# IRBeaconBlasterSchematic.net
KiCad netlist of a schematic drawn in Altium Designer
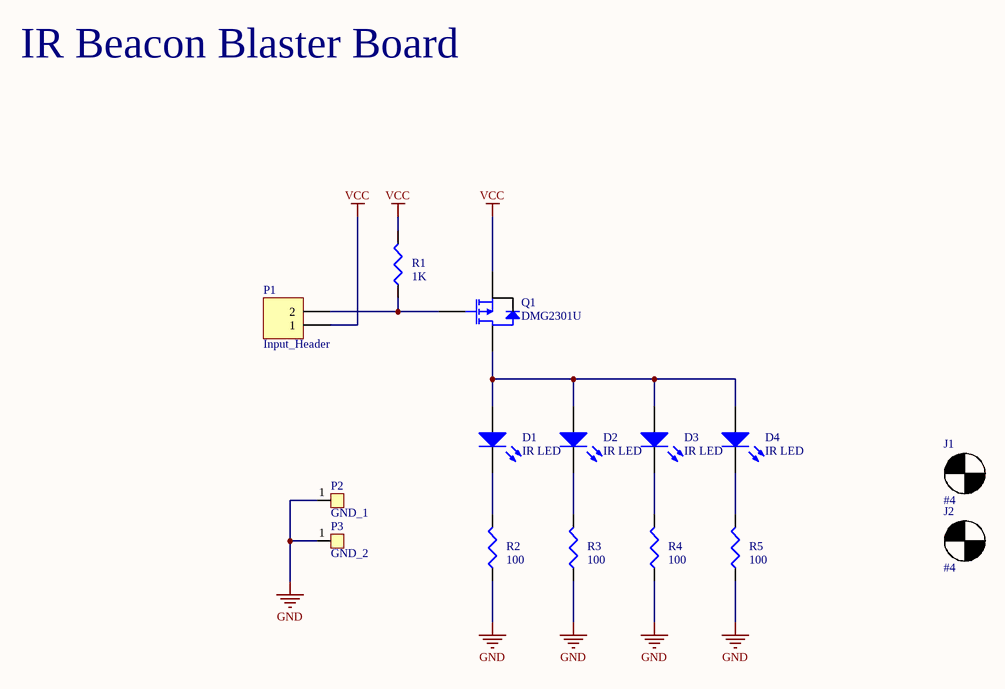
[diagram p0: IRBeaconBlasterSchematic.SchDoc]

(export (version "E")
  (design (tool "Eeschema 10.0.6"))
  (components
    (comp (ref "D1") (value "IR LED") (footprint "LED_PTH_3mm") (libsource (lib "mrone") (part "LED")))
    (comp (ref "D2") (value "IR LED") (footprint "LED_PTH_3mm") (libsource (lib "mrone") (part "LED")))
    (comp (ref "D3") (value "IR LED") (footprint "LED_PTH_3mm") (libsource (lib "mrone") (part "LED")))
    (comp (ref "D4") (value "IR LED") (footprint "LED_PTH_3mm") (libsource (lib "mrone") (part "LED")))
    (comp (ref "J1")
      (value "#4")
      (footprint "#4_Screw_Hole")
      (description "A mechanical hole for mounting the board")
      (libsource (lib "mrone") (part "Mechanical_Hole"))
    )
    (comp (ref "J2")
      (value "#4")
      (footprint "#4_Screw_Hole")
      (description "A mechanical hole for mounting the board")
      (libsource (lib "mrone") (part "Mechanical_Hole"))
    )
    (comp (ref "P1")
      (value "Input_Header")
      (footprint "HDR1X2")
      (description "Header, 2-Pin")
      (fields (field (name "PUBLISHER") "Altium Limited"))
      (libsource (lib "mrone") (part "Header 2"))
    )
    (comp (ref "P2") (value "GND_1") (footprint "HDR1X1") (libsource (lib "mrone") (part "Header 1x1")))
    (comp (ref "P3") (value "GND_2") (footprint "HDR1X1") (libsource (lib "mrone") (part "Header 1x1")))
    (comp (ref "Q1") (value "DMG2301U") (footprint "SOT-23") (libsource (lib "mrone") (part "P-Mosfet")))
    (comp (ref "R1")
      (value "1K")
      (footprint "J1-0603")
      (description "Resistor")
      (fields (field (name "PUBLISHER") "Altium Limited"))
      (libsource (lib "Miscellaneous Devices") (part "Res3"))
    )
    (comp (ref "R2")
      (value "100")
      (footprint "J1-0603")
      (description "Resistor")
      (fields (field (name "Comment") "Res3") (field (name "PUBLISHER") "Altium Limited"))
      (libsource (lib "Miscellaneous Devices") (part "Res3"))
    )
    (comp (ref "R3")
      (value "100")
      (footprint "J1-0603")
      (description "Resistor")
      (fields (field (name "Comment") "Res3") (field (name "PUBLISHER") "Altium Limited"))
      (libsource (lib "Miscellaneous Devices") (part "Res3"))
    )
    (comp (ref "R4")
      (value "100")
      (footprint "J1-0603")
      (description "Resistor")
      (fields (field (name "Comment") "Res3") (field (name "PUBLISHER") "Altium Limited"))
      (libsource (lib "Miscellaneous Devices") (part "Res3"))
    )
    (comp (ref "R5")
      (value "100")
      (footprint "J1-0603")
      (description "Resistor")
      (fields (field (name "Comment") "Res3") (field (name "PUBLISHER") "Altium Limited"))
      (libsource (lib "Miscellaneous Devices") (part "Res3"))
    )
  )
  (nets
    (net (code "1") (name "GND") (class "Default")
      (node (ref "P2") (pin "1") (pintype "passive"))
      (node (ref "P3") (pin "1") (pintype "passive"))
      (node (ref "R2") (pin "1") (pinfunction "1_1") (pintype "passive"))
      (node (ref "R3") (pin "1") (pinfunction "1_1") (pintype "passive"))
      (node (ref "R4") (pin "1") (pinfunction "1_1") (pintype "passive"))
      (node (ref "R5") (pin "1") (pinfunction "1_1") (pintype "passive"))
    )
    (net (code "2") (name "Net-(D1-A)") (class "Default")
      (node (ref "D1") (pin "1") (pinfunction "A_1") (pintype "passive"))
      (node (ref "D2") (pin "1") (pinfunction "A_1") (pintype "passive"))
      (node (ref "D3") (pin "1") (pinfunction "A_1") (pintype "passive"))
      (node (ref "D4") (pin "1") (pinfunction "A_1") (pintype "passive"))
      (node (ref "Q1") (pin "3") (pinfunction "D_3") (pintype "passive"))
    )
    (net (code "3") (name "Net-(D1-K)") (class "Default")
      (node (ref "D1") (pin "2") (pinfunction "K_2") (pintype "passive"))
      (node (ref "R2") (pin "2") (pinfunction "2_2") (pintype "passive"))
    )
    (net (code "4") (name "Net-(D2-K)") (class "Default")
      (node (ref "D2") (pin "2") (pinfunction "K_2") (pintype "passive"))
      (node (ref "R3") (pin "2") (pinfunction "2_2") (pintype "passive"))
    )
    (net (code "5") (name "Net-(D3-K)") (class "Default")
      (node (ref "D3") (pin "2") (pinfunction "K_2") (pintype "passive"))
      (node (ref "R4") (pin "2") (pinfunction "2_2") (pintype "passive"))
    )
    (net (code "6") (name "Net-(D4-K)") (class "Default")
      (node (ref "D4") (pin "2") (pinfunction "K_2") (pintype "passive"))
      (node (ref "R5") (pin "2") (pinfunction "2_2") (pintype "passive"))
    )
    (net (code "7") (name "Net-(Q1-G)") (class "Default")
      (node (ref "P1") (pin "2") (pinfunction "2_2") (pintype "passive"))
      (node (ref "Q1") (pin "1") (pinfunction "G_1") (pintype "passive"))
      (node (ref "R1") (pin "1") (pinfunction "1_1") (pintype "passive"))
    )
    (net (code "8") (name "VCC") (class "Default")
      (node (ref "P1") (pin "1") (pinfunction "1_1") (pintype "passive"))
      (node (ref "Q1") (pin "2") (pinfunction "S_2") (pintype "passive"))
      (node (ref "R1") (pin "2") (pinfunction "2_2") (pintype "passive"))
    )
  )
)
